# 0_Overview.net
KiCad netlist of a schematic drawn in Altium Designer
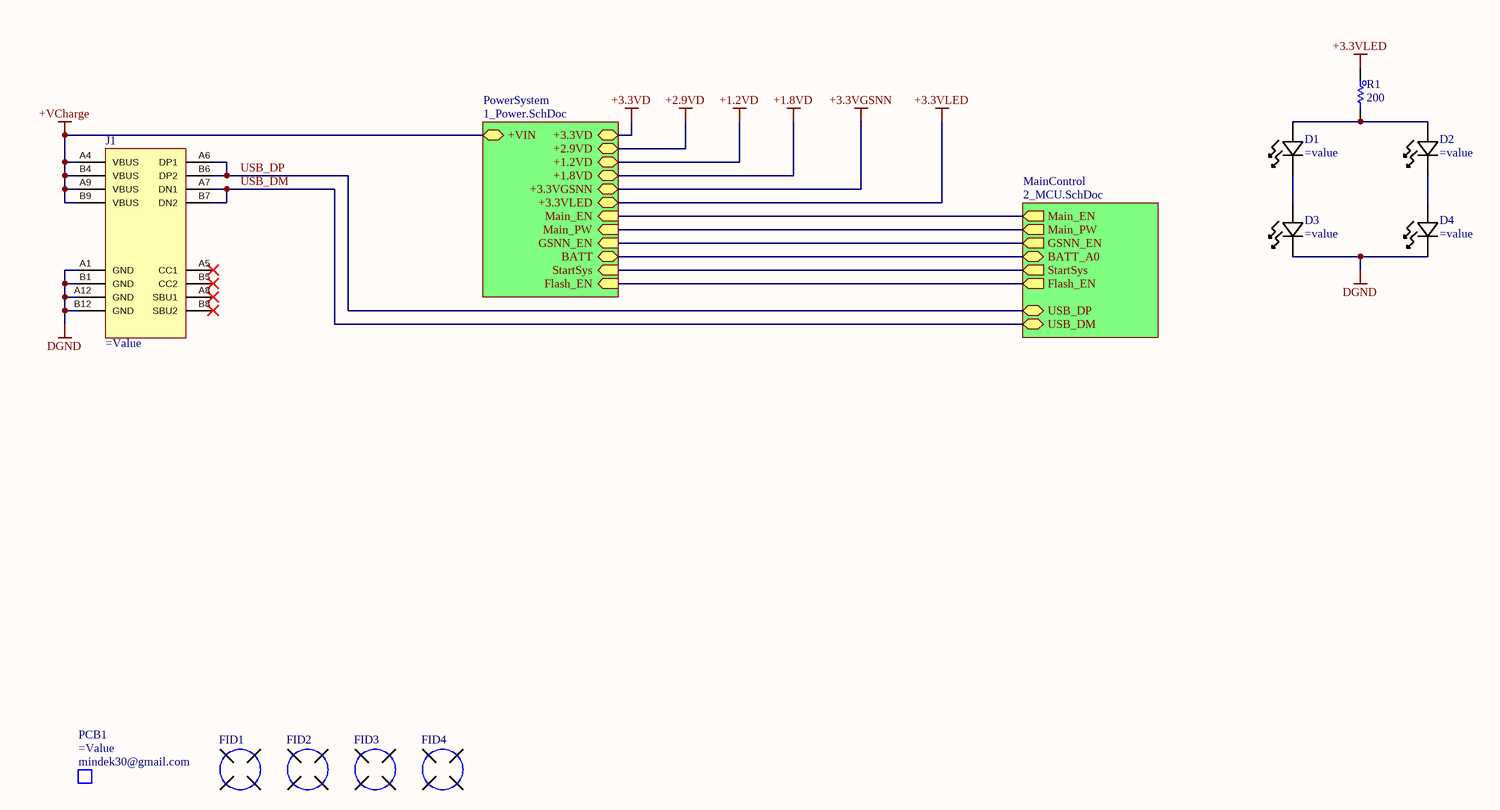
[diagram p0: 0_Overview.SchDoc]

(export (version "E")
  (design (tool "Eeschema 10.0.6"))
  (components
    (comp (ref "D1")
      (value "~")
      (footprint "LED_0VS75000_WRE")
      (description "LED BLUE CLEAR 0603 SMD")
      (fields (field (name "MANUFACTURER") "Wurth Electronics") (field (name "PARTNUMBER") "150060VS75000"))
      (libsource (lib "UUSymbol") (part "D_LED_150060BS75000"))
    )
    (comp (ref "D2")
      (value "~")
      (footprint "LED_0VS75000_WRE")
      (description "LED BLUE CLEAR 0603 SMD")
      (fields (field (name "MANUFACTURER") "Wurth Electronics") (field (name "PARTNUMBER") "150060VS75000"))
      (libsource (lib "UUSymbol") (part "D_LED_150060BS75000"))
    )
    (comp (ref "D3")
      (value "~")
      (footprint "LED_0VS75000_WRE")
      (description "LED BLUE CLEAR 0603 SMD")
      (fields (field (name "MANUFACTURER") "Wurth Electronics") (field (name "PARTNUMBER") "150060VS75000"))
      (libsource (lib "UUSymbol") (part "D_LED_150060BS75000"))
    )
    (comp (ref "D4")
      (value "~")
      (footprint "LED_0VS75000_WRE")
      (description "LED BLUE CLEAR 0603 SMD")
      (fields (field (name "MANUFACTURER") "Wurth Electronics") (field (name "PARTNUMBER") "150060VS75000"))
      (libsource (lib "UUSymbol") (part "D_LED_150060BS75000"))
    )
    (comp (ref "FID1")
      (value "FIDUCIAL")
      (footprint "FID")
      (description "Fiducial")
      (fields (field (name "MANUFACTURER") "mindek30@gmail.com") (field (name "PARTNUMBER") "_"))
      (libsource (lib "UUSymbol") (part "FID_FIDUCIAL"))
    )
    (comp (ref "FID2")
      (value "FIDUCIAL")
      (footprint "FID")
      (description "Fiducial")
      (fields (field (name "MANUFACTURER") "mindek30@gmail.com") (field (name "PARTNUMBER") "_"))
      (libsource (lib "UUSymbol") (part "FID_FIDUCIAL"))
    )
    (comp (ref "FID3")
      (value "FIDUCIAL")
      (footprint "FID")
      (description "Fiducial")
      (fields (field (name "MANUFACTURER") "mindek30@gmail.com") (field (name "PARTNUMBER") "_"))
      (libsource (lib "UUSymbol") (part "FID_FIDUCIAL"))
    )
    (comp (ref "FID4")
      (value "FIDUCIAL")
      (footprint "FID")
      (description "Fiducial")
      (fields (field (name "MANUFACTURER") "mindek30@gmail.com") (field (name "PARTNUMBER") "_"))
      (libsource (lib "UUSymbol") (part "FID_FIDUCIAL"))
    )
    (comp (ref "J1")
      (value "~")
      (footprint "2137160001_MOL_2137160001(Primary)")
      (description "CONN RCPT USB2.0 TYPE C 24POS RA")
      (fields (field (name "PARTNUMBER") "2137160001") (field (name "MANUFACTURER") "Molex"))
      (libsource (lib "UUSymbol") (part "CON_USBC"))
    )
    (comp (ref "PCB1")
      (value "~")
      (description "BARE PCB")
      (fields (field (name "MANUFACTURER") "mindek30@gmail.com") (field (name "PARTNUMBER") "_"))
      (libsource (lib "UUSymbol") (part "PCB_Bare"))
    )
    (comp (ref "R1")
      (value "200")
      (footprint "R_2512")
      (description "Resistor")
      (fields (field (name "MANUFACTURER") "Vishay") (field (name "PARTNUMBER") "EXB-2HV472JV"))
      (libsource (lib "UUSymbol") (part "R_Resister"))
    )
  )
  (nets
    (net (code "6") (name "+3.3VLED") (class "Default")
      (node (ref "R1") (pin "1") (pinfunction "1_1") (pintype "passive"))
    )
    (net (code "7") (name "+VCharge") (class "Default")
      (node (ref "J1") (pin "A4") (pinfunction "VBUS_A4") (pintype "passive"))
      (node (ref "J1") (pin "A9") (pinfunction "VBUS_A9") (pintype "passive"))
      (node (ref "J1") (pin "B4") (pinfunction "VBUS_B4") (pintype "passive"))
      (node (ref "J1") (pin "B9") (pinfunction "VBUS_B9") (pintype "passive"))
    )
    (net (code "14") (name "/USB_DM") (class "Default")
      (node (ref "J1") (pin "A7") (pinfunction "DN1_A7") (pintype "passive"))
      (node (ref "J1") (pin "B7") (pinfunction "DN2_B7") (pintype "passive"))
    )
    (net (code "15") (name "/USB_DP") (class "Default")
      (node (ref "J1") (pin "A6") (pinfunction "DP1_A6") (pintype "passive"))
      (node (ref "J1") (pin "B6") (pinfunction "DP2_B6") (pintype "passive"))
    )
    (net (code "16") (name "DGND") (class "Default")
      (node (ref "D3") (pin "2") (pinfunction "2_2") (pintype "passive"))
      (node (ref "D4") (pin "2") (pinfunction "2_2") (pintype "passive"))
      (node (ref "J1") (pin "A1") (pinfunction "GND_A1") (pintype "passive"))
      (node (ref "J1") (pin "A12") (pinfunction "GND_A12") (pintype "passive"))
      (node (ref "J1") (pin "B1") (pinfunction "GND_B1") (pintype "passive"))
      (node (ref "J1") (pin "B12") (pinfunction "GND_B12") (pintype "passive"))
    )
    (net (code "17") (name "Net-(D1-Pad1)") (class "Default")
      (node (ref "D1") (pin "1") (pinfunction "1_1") (pintype "passive"))
      (node (ref "D2") (pin "1") (pinfunction "1_1") (pintype "passive"))
      (node (ref "R1") (pin "2") (pinfunction "2_2") (pintype "passive"))
    )
    (net (code "18") (name "Net-(D1-Pad2)") (class "Default")
      (node (ref "D1") (pin "2") (pinfunction "2_2") (pintype "passive"))
      (node (ref "D3") (pin "1") (pinfunction "1_1") (pintype "passive"))
    )
    (net (code "19") (name "Net-(D2-Pad2)") (class "Default")
      (node (ref "D2") (pin "2") (pinfunction "2_2") (pintype "passive"))
      (node (ref "D4") (pin "1") (pinfunction "1_1") (pintype "passive"))
    )
    (net (code "20") (name "unconnected-(J1-CC1-PadA5)") (class "Default")
      (node (ref "J1") (pin "A5") (pinfunction "CC1_A5") (pintype "passive+no_connect"))
    )
    (net (code "21") (name "unconnected-(J1-CC2-PadB5)") (class "Default")
      (node (ref "J1") (pin "B5") (pinfunction "CC2_B5") (pintype "passive+no_connect"))
    )
    (net (code "22") (name "unconnected-(J1-SBU1-PadA8)") (class "Default")
      (node (ref "J1") (pin "A8") (pinfunction "SBU1_A8") (pintype "passive+no_connect"))
    )
    (net (code "23") (name "unconnected-(J1-SBU2-PadB8)") (class "Default")
      (node (ref "J1") (pin "B8") (pinfunction "SBU2_B8") (pintype "passive+no_connect"))
    )
  )
)
